# Pro_Shield_1.net
KiCad netlist of a schematic drawn in EAGLE
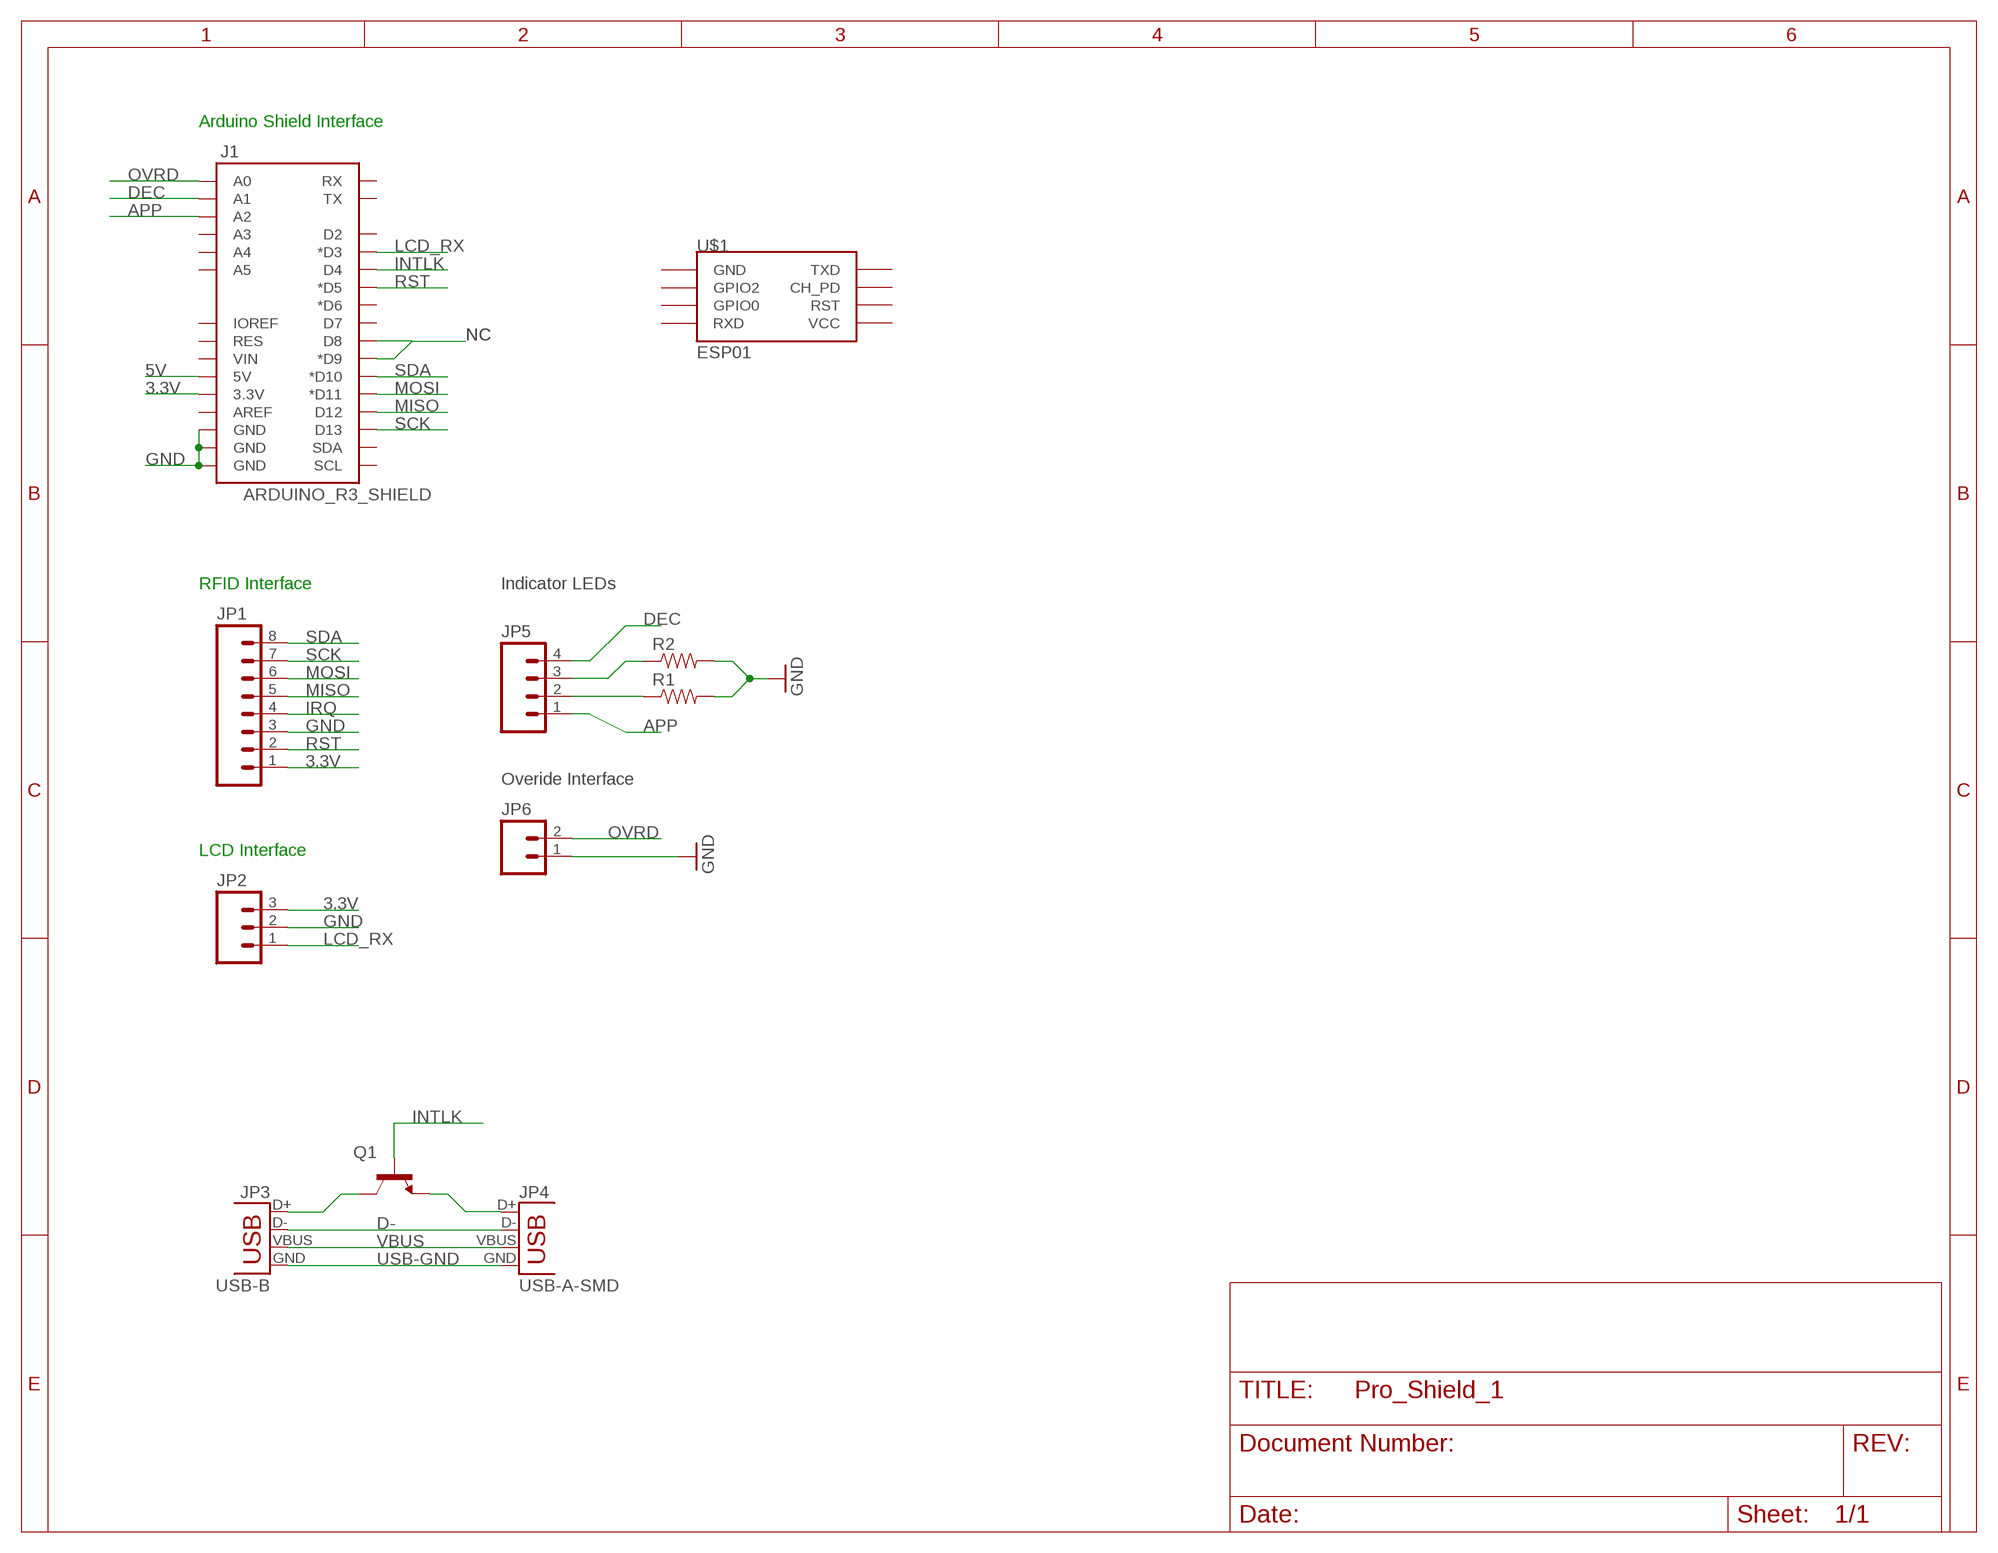
[diagram p0: schematic, sheet 1]

(export (version "E")
  (design (tool "Eeschema 10.0.6"))
  (components
    (comp (ref "J1")
      (value "ARDUINO_R3_SHIELD")
      (footprint "eagle-import:UNO_R3_SHIELD")
      (libsource (lib "eagle-import") (part "ARDUINO_R3_SHIELD"))
    )
    (comp (ref "JP1")
      (value "M08LONGPADS")
      (footprint "eagle-import:1X08_LONGPADS")
      (libsource (lib "eagle-import") (part "M08LONGPADS"))
    )
    (comp (ref "JP2")
      (value "M03LONGPADS")
      (footprint "eagle-import:1X03_LONGPADS")
      (libsource (lib "eagle-import") (part "M03LONGPADS"))
    )
    (comp (ref "JP3")
      (value "USB-B")
      (footprint "eagle-import:USB-B-PTH")
      (libsource (lib "eagle-import") (part "USBPTH"))
    )
    (comp (ref "JP4")
      (value "USB-A-SMD")
      (footprint "eagle-import:USB-A-S-NOSILK-FEMALE")
      (libsource (lib "eagle-import") (part "USB-A-SMD"))
    )
    (comp (ref "JP5")
      (value "M04LONGPADS")
      (footprint "eagle-import:1X04_LONGPADS")
      (libsource (lib "eagle-import") (part "M04LONGPADS"))
    )
    (comp (ref "JP6")
      (value "M02LOCK_LONGPADS")
      (footprint "eagle-import:1X02_LOCK_LONGPADS")
      (libsource (lib "eagle-import") (part "M02LOCK_LONGPADS"))
    )
    (comp (ref "Q1")
      (value "TRANSISTOR_NPNBC547")
      (footprint "eagle-import:TO-92-AMMO")
      (libsource (lib "eagle-import") (part "TRANSISTOR_NPNBC547"))
    )
    (comp (ref "R1")
      (value "RESISTORPTH-1/4W")
      (footprint "eagle-import:AXIAL-0.4")
      (libsource (lib "eagle-import") (part "RESISTORPTH-1/4W"))
    )
    (comp (ref "R2")
      (value "RESISTORPTH-1/4W")
      (footprint "eagle-import:AXIAL-0.4")
      (libsource (lib "eagle-import") (part "RESISTORPTH-1/4W"))
    )
    (comp (ref "U$1")
      (value "ESP01")
      (footprint "eagle-import:ESP01")
      (libsource (lib "eagle-import") (part "ESP01"))
    )
  )
  (nets
    (net (code "1") (name "/3.3V") (class "Default")
      (node (ref "J1") (pin "3.3V") (pinfunction "3.3V_3.3V") (pintype "bidirectional"))
      (node (ref "JP1") (pin "1") (pinfunction "1_1") (pintype "passive"))
      (node (ref "JP2") (pin "3") (pinfunction "3_3") (pintype "passive"))
    )
    (net (code "2") (name "/5V") (class "Default")
      (node (ref "J1") (pin "5V") (pinfunction "5V_5V") (pintype "bidirectional"))
    )
    (net (code "3") (name "/APP") (class "Default")
      (node (ref "J1") (pin "A2") (pinfunction "A2_A2") (pintype "bidirectional"))
      (node (ref "JP5") (pin "1") (pinfunction "1_1") (pintype "passive"))
    )
    (net (code "4") (name "/D-") (class "Default")
      (node (ref "JP3") (pin "D-") (pinfunction "D-_D-") (pintype "bidirectional"))
      (node (ref "JP4") (pin "D-") (pinfunction "D-_D-") (pintype "bidirectional"))
    )
    (net (code "5") (name "/DEC") (class "Default")
      (node (ref "J1") (pin "A1") (pinfunction "A1_A1") (pintype "bidirectional"))
      (node (ref "JP5") (pin "4") (pinfunction "4_4") (pintype "passive"))
    )
    (net (code "6") (name "/INTLK") (class "Default")
      (node (ref "J1") (pin "D4") (pinfunction "D4_D4") (pintype "bidirectional"))
      (node (ref "Q1") (pin "2") (pinfunction "B_2") (pintype "passive"))
    )
    (net (code "7") (name "/IRQ") (class "Default")
      (node (ref "JP1") (pin "4") (pinfunction "4_4") (pintype "passive"))
    )
    (net (code "8") (name "/LCD_RX") (class "Default")
      (node (ref "J1") (pin "D3") (pinfunction "*D3_D3") (pintype "bidirectional"))
      (node (ref "JP2") (pin "1") (pinfunction "1_1") (pintype "passive"))
    )
    (net (code "9") (name "/MISO") (class "Default")
      (node (ref "J1") (pin "D12") (pinfunction "D12_D12") (pintype "bidirectional"))
      (node (ref "JP1") (pin "5") (pinfunction "5_5") (pintype "passive"))
    )
    (net (code "10") (name "/MOSI") (class "Default")
      (node (ref "J1") (pin "D11") (pinfunction "*D11_D11") (pintype "bidirectional"))
      (node (ref "JP1") (pin "6") (pinfunction "6_6") (pintype "passive"))
    )
    (net (code "11") (name "/OVRD") (class "Default")
      (node (ref "J1") (pin "A0") (pinfunction "A0_A0") (pintype "bidirectional"))
      (node (ref "JP6") (pin "2") (pinfunction "2_2") (pintype "passive"))
    )
    (net (code "12") (name "/RST") (class "Default")
      (node (ref "J1") (pin "D5") (pinfunction "*D5_D5") (pintype "bidirectional"))
      (node (ref "JP1") (pin "2") (pinfunction "2_2") (pintype "passive"))
    )
    (net (code "13") (name "/SCK") (class "Default")
      (node (ref "J1") (pin "D13") (pinfunction "D13_D13") (pintype "bidirectional"))
      (node (ref "JP1") (pin "7") (pinfunction "7_7") (pintype "passive"))
    )
    (net (code "14") (name "/SDA") (class "Default")
      (node (ref "J1") (pin "D10") (pinfunction "*D10_D10") (pintype "bidirectional"))
      (node (ref "JP1") (pin "8") (pinfunction "8_8") (pintype "passive"))
    )
    (net (code "15") (name "/USB-GND") (class "Default")
      (node (ref "JP3") (pin "GND") (pinfunction "GND_GND") (pintype "bidirectional"))
      (node (ref "JP4") (pin "GND") (pinfunction "GND_GND") (pintype "bidirectional"))
    )
    (net (code "16") (name "/VBUS") (class "Default")
      (node (ref "JP3") (pin "VBUS") (pinfunction "VBUS_VBUS") (pintype "bidirectional"))
      (node (ref "JP4") (pin "VBUS") (pinfunction "VBUS_VBUS") (pintype "bidirectional"))
    )
    (net (code "17") (name "GND") (class "Default")
      (node (ref "J1") (pin "GND@0") (pinfunction "GND_GND@0") (pintype "bidirectional"))
      (node (ref "J1") (pin "GND@1") (pinfunction "GND_GND@1") (pintype "bidirectional"))
      (node (ref "J1") (pin "GND@2") (pinfunction "GND_GND@2") (pintype "bidirectional"))
      (node (ref "JP1") (pin "3") (pinfunction "3_3") (pintype "passive"))
      (node (ref "JP2") (pin "2") (pinfunction "2_2") (pintype "passive"))
      (node (ref "JP6") (pin "1") (pinfunction "1_1") (pintype "passive"))
      (node (ref "R1") (pin "P$2") (pinfunction "2_P$2") (pintype "passive"))
      (node (ref "R2") (pin "P$2") (pinfunction "2_P$2") (pintype "passive"))
    )
    (net (code "18") (name "Net-(J1-*D9)") (class "Default")
      (node (ref "J1") (pin "D8") (pinfunction "D8_D8") (pintype "bidirectional"))
      (node (ref "J1") (pin "D9") (pinfunction "*D9_D9") (pintype "bidirectional"))
    )
    (net (code "19") (name "Net-(Q1-C)") (class "Default")
      (node (ref "JP3") (pin "D+") (pinfunction "D+_D+") (pintype "bidirectional"))
      (node (ref "Q1") (pin "1") (pinfunction "C_1") (pintype "passive"))
    )
    (net (code "20") (name "Net-(Q1-E)") (class "Default")
      (node (ref "JP4") (pin "D+") (pinfunction "D+_D+") (pintype "bidirectional"))
      (node (ref "Q1") (pin "3") (pinfunction "E_3") (pintype "passive"))
    )
    (net (code "21") (name "Net-(R1-1)") (class "Default")
      (node (ref "JP5") (pin "2") (pinfunction "2_2") (pintype "passive"))
      (node (ref "R1") (pin "P$1") (pinfunction "1_P$1") (pintype "passive"))
    )
    (net (code "22") (name "Net-(R2-1)") (class "Default")
      (node (ref "JP5") (pin "3") (pinfunction "3_3") (pintype "passive"))
      (node (ref "R2") (pin "P$1") (pinfunction "1_P$1") (pintype "passive"))
    )
    (net (code "23") (name "unconnected-(J1-*D6-PadD6)") (class "Default")
      (node (ref "J1") (pin "D6") (pinfunction "*D6_D6") (pintype "bidirectional"))
    )
    (net (code "24") (name "unconnected-(J1-PadA3)") (class "Default")
      (node (ref "J1") (pin "A3") (pinfunction "A3_A3") (pintype "bidirectional"))
    )
    (net (code "25") (name "unconnected-(J1-PadA4)") (class "Default")
      (node (ref "J1") (pin "A4") (pinfunction "A4_A4") (pintype "bidirectional"))
    )
    (net (code "26") (name "unconnected-(J1-PadA5)") (class "Default")
      (node (ref "J1") (pin "A5") (pinfunction "A5_A5") (pintype "bidirectional"))
    )
    (net (code "27") (name "unconnected-(J1-PadAREF)") (class "Default")
      (node (ref "J1") (pin "AREF") (pinfunction "AREF_AREF") (pintype "bidirectional"))
    )
    (net (code "28") (name "unconnected-(J1-PadD2)") (class "Default")
      (node (ref "J1") (pin "D2") (pinfunction "D2_D2") (pintype "bidirectional"))
    )
    (net (code "29") (name "unconnected-(J1-PadD7)") (class "Default")
      (node (ref "J1") (pin "D7") (pinfunction "D7_D7") (pintype "bidirectional"))
    )
    (net (code "30") (name "unconnected-(J1-PadIOREF)") (class "Default")
      (node (ref "J1") (pin "IOREF") (pinfunction "IOREF_IOREF") (pintype "bidirectional"))
    )
    (net (code "31") (name "unconnected-(J1-PadRES)") (class "Default")
      (node (ref "J1") (pin "RES") (pinfunction "RES_RES") (pintype "bidirectional"))
    )
    (net (code "32") (name "unconnected-(J1-PadRX)") (class "Default")
      (node (ref "J1") (pin "RX") (pinfunction "RX_RX") (pintype "bidirectional"))
    )
    (net (code "33") (name "unconnected-(J1-PadSCL)") (class "Default")
      (node (ref "J1") (pin "SCL") (pinfunction "SCL_SCL") (pintype "bidirectional"))
    )
    (net (code "34") (name "unconnected-(J1-PadSDA)") (class "Default")
      (node (ref "J1") (pin "SDA") (pinfunction "SDA_SDA") (pintype "bidirectional"))
    )
    (net (code "35") (name "unconnected-(J1-PadTX)") (class "Default")
      (node (ref "J1") (pin "TX") (pinfunction "TX_TX") (pintype "bidirectional"))
    )
    (net (code "36") (name "unconnected-(J1-PadVIN)") (class "Default")
      (node (ref "J1") (pin "VIN") (pinfunction "VIN_VIN") (pintype "bidirectional"))
    )
    (net (code "37") (name "unconnected-(U$1-PadCH_PD)") (class "Default")
      (node (ref "U$1") (pin "CH_PD") (pinfunction "CH_PD_CH_PD") (pintype "bidirectional"))
    )
    (net (code "38") (name "unconnected-(U$1-PadGND)") (class "Default")
      (node (ref "U$1") (pin "GND") (pinfunction "GND_GND") (pintype "bidirectional"))
    )
    (net (code "39") (name "unconnected-(U$1-PadGPIO0)") (class "Default")
      (node (ref "U$1") (pin "GPIO0") (pinfunction "GPIO0_GPIO0") (pintype "bidirectional"))
    )
    (net (code "40") (name "unconnected-(U$1-PadGPIO2)") (class "Default")
      (node (ref "U$1") (pin "GPIO2") (pinfunction "GPIO2_GPIO2") (pintype "bidirectional"))
    )
    (net (code "41") (name "unconnected-(U$1-PadRST)") (class "Default")
      (node (ref "U$1") (pin "RST") (pinfunction "RST_RST") (pintype "bidirectional"))
    )
    (net (code "42") (name "unconnected-(U$1-PadVCC)") (class "Default")
      (node (ref "U$1") (pin "VCC") (pinfunction "VCC_VCC") (pintype "bidirectional"))
    )
    (net (code "43") (name "unconnected-(U$1-RXD-PadRX)") (class "Default")
      (node (ref "U$1") (pin "RX") (pinfunction "RXD_RX") (pintype "bidirectional"))
    )
    (net (code "44") (name "unconnected-(U$1-TXD-PadTX)") (class "Default")
      (node (ref "U$1") (pin "TX") (pinfunction "TXD_TX") (pintype "bidirectional"))
    )
  )
)
